# Extra.net
KiCad netlist of a schematic drawn in Altium Designer
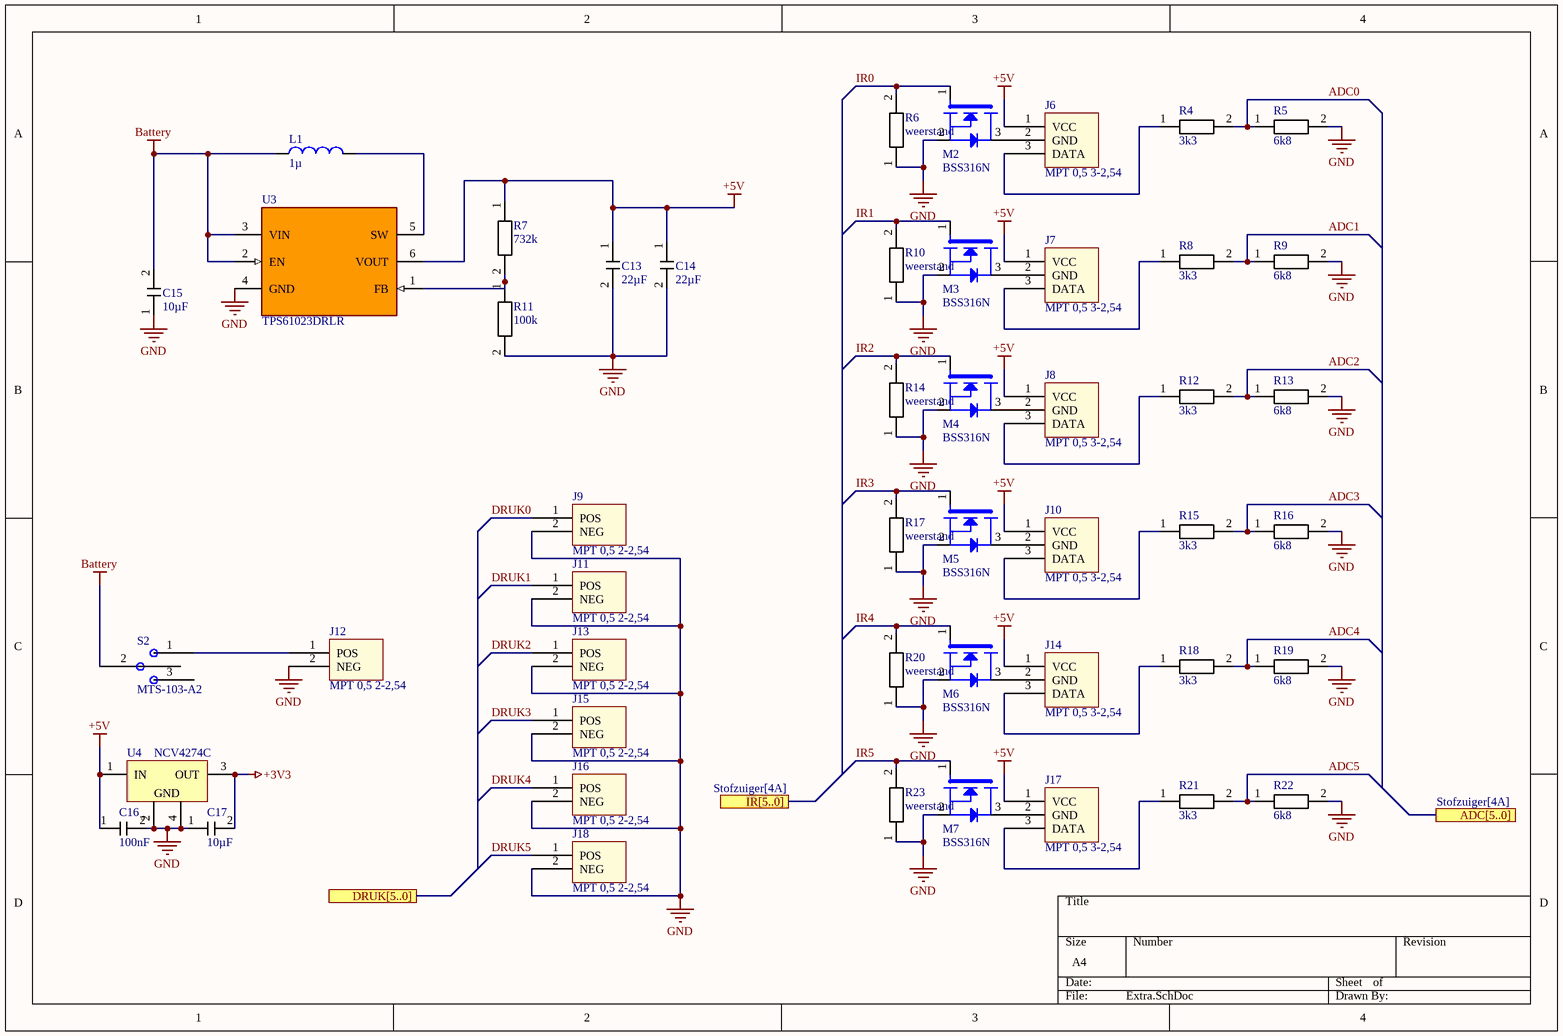
[diagram p0: Extra.SchDoc]

(export (version "E")
  (design (tool "Eeschema 10.0.6"))
  (components
    (comp (ref "C13") (value "22µF") (footprint "0603") (libsource (lib "Schlib1") (part "cap")))
    (comp (ref "C14") (value "22µF") (footprint "0603") (libsource (lib "Schlib1") (part "cap")))
    (comp (ref "C15") (value "10µF") (footprint "0603") (libsource (lib "Schlib1") (part "cap")))
    (comp (ref "C16") (value "100nF") (footprint "0603") (libsource (lib "Schlib1") (part "cap")))
    (comp (ref "C17") (value "10µF") (footprint "0603") (libsource (lib "Schlib1") (part "cap")))
    (comp (ref "J6")
      (value "MPT 0,5 3-2,54")
      (footprint "MPT 0,5 3-2,54")
      (libsource (lib "Schlib1") (part "MPT 0,5 3-2,54"))
    )
    (comp (ref "J7")
      (value "MPT 0,5 3-2,54")
      (footprint "MPT 0,5 3-2,54")
      (libsource (lib "Schlib1") (part "MPT 0,5 3-2,54"))
    )
    (comp (ref "J8")
      (value "MPT 0,5 3-2,54")
      (footprint "MPT 0,5 3-2,54")
      (libsource (lib "Schlib1") (part "MPT 0,5 3-2,54"))
    )
    (comp (ref "J9")
      (value "MPT 0,5 2-2,54")
      (footprint "MPT 0,5 2-2,54")
      (libsource (lib "Schlib1") (part "MPT 0,5 2-2,54"))
    )
    (comp (ref "J10")
      (value "MPT 0,5 3-2,54")
      (footprint "MPT 0,5 3-2,54")
      (libsource (lib "Schlib1") (part "MPT 0,5 3-2,54"))
    )
    (comp (ref "J11")
      (value "MPT 0,5 2-2,54")
      (footprint "MPT 0,5 2-2,54")
      (libsource (lib "Schlib1") (part "MPT 0,5 2-2,54"))
    )
    (comp (ref "J12")
      (value "MPT 0,5 2-2,54")
      (footprint "MPT 0,5 2-2,54")
      (libsource (lib "Schlib1") (part "MPT 0,5 2-2,54"))
    )
    (comp (ref "J13")
      (value "MPT 0,5 2-2,54")
      (footprint "MPT 0,5 2-2,54")
      (libsource (lib "Schlib1") (part "MPT 0,5 2-2,54"))
    )
    (comp (ref "J14")
      (value "MPT 0,5 3-2,54")
      (footprint "MPT 0,5 3-2,54")
      (libsource (lib "Schlib1") (part "MPT 0,5 3-2,54"))
    )
    (comp (ref "J15")
      (value "MPT 0,5 2-2,54")
      (footprint "MPT 0,5 2-2,54")
      (libsource (lib "Schlib1") (part "MPT 0,5 2-2,54"))
    )
    (comp (ref "J16")
      (value "MPT 0,5 2-2,54")
      (footprint "MPT 0,5 2-2,54")
      (libsource (lib "Schlib1") (part "MPT 0,5 2-2,54"))
    )
    (comp (ref "J17")
      (value "MPT 0,5 3-2,54")
      (footprint "MPT 0,5 3-2,54")
      (libsource (lib "Schlib1") (part "MPT 0,5 3-2,54"))
    )
    (comp (ref "J18")
      (value "MPT 0,5 2-2,54")
      (footprint "MPT 0,5 2-2,54")
      (libsource (lib "Schlib1") (part "MPT 0,5 2-2,54"))
    )
    (comp (ref "L1") (value "1µ") (footprint "0603") (libsource (lib "Schlib1") (part "spoel")))
    (comp (ref "M2") (value "BSS316N") (footprint "BSS316N") (libsource (lib "Schlib1") (part "BSS316N")))
    (comp (ref "M3") (value "BSS316N") (footprint "BSS316N") (libsource (lib "Schlib1") (part "BSS316N")))
    (comp (ref "M4") (value "BSS316N") (footprint "BSS316N") (libsource (lib "Schlib1") (part "BSS316N")))
    (comp (ref "M5") (value "BSS316N") (footprint "BSS316N") (libsource (lib "Schlib1") (part "BSS316N")))
    (comp (ref "M6") (value "BSS316N") (footprint "BSS316N") (libsource (lib "Schlib1") (part "BSS316N")))
    (comp (ref "M7") (value "BSS316N") (footprint "BSS316N") (libsource (lib "Schlib1") (part "BSS316N")))
    (comp (ref "R4") (value "3k3") (footprint "0603") (libsource (lib "Schlib1") (part "weerstand")))
    (comp (ref "R5") (value "6k8") (footprint "0603") (libsource (lib "Schlib1") (part "weerstand")))
    (comp (ref "R6") (value "weerstand") (footprint "0603") (libsource (lib "Schlib1") (part "weerstand")))
    (comp (ref "R7") (value "732k") (footprint "0603") (libsource (lib "Schlib1") (part "weerstand")))
    (comp (ref "R8") (value "3k3") (footprint "0603") (libsource (lib "Schlib1") (part "weerstand")))
    (comp (ref "R9") (value "6k8") (footprint "0603") (libsource (lib "Schlib1") (part "weerstand")))
    (comp (ref "R10") (value "weerstand") (footprint "0603") (libsource (lib "Schlib1") (part "weerstand")))
    (comp (ref "R11") (value "100k") (footprint "0603") (libsource (lib "Schlib1") (part "weerstand")))
    (comp (ref "R12") (value "3k3") (footprint "0603") (libsource (lib "Schlib1") (part "weerstand")))
    (comp (ref "R13") (value "6k8") (footprint "0603") (libsource (lib "Schlib1") (part "weerstand")))
    (comp (ref "R14") (value "weerstand") (footprint "0603") (libsource (lib "Schlib1") (part "weerstand")))
    (comp (ref "R15") (value "3k3") (footprint "0603") (libsource (lib "Schlib1") (part "weerstand")))
    (comp (ref "R16") (value "6k8") (footprint "0603") (libsource (lib "Schlib1") (part "weerstand")))
    (comp (ref "R17") (value "weerstand") (footprint "0603") (libsource (lib "Schlib1") (part "weerstand")))
    (comp (ref "R18") (value "3k3") (footprint "0603") (libsource (lib "Schlib1") (part "weerstand")))
    (comp (ref "R19") (value "6k8") (footprint "0603") (libsource (lib "Schlib1") (part "weerstand")))
    (comp (ref "R20") (value "weerstand") (footprint "0603") (libsource (lib "Schlib1") (part "weerstand")))
    (comp (ref "R21") (value "3k3") (footprint "0603") (libsource (lib "Schlib1") (part "weerstand")))
    (comp (ref "R22") (value "6k8") (footprint "0603") (libsource (lib "Schlib1") (part "weerstand")))
    (comp (ref "R23") (value "weerstand") (footprint "0603") (libsource (lib "Schlib1") (part "weerstand")))
    (comp (ref "S2")
      (value "MTS-103-A2")
      (footprint "MTS-103-A2")
      (libsource (lib "Schlib1") (part "MTS-103-A2"))
    )
    (comp (ref "U3")
      (value "TPS61023DRLR")
      (footprint "TPS61023DRLR")
      (libsource (lib "Schlib1") (part "TPS61023DRLR"))
    )
    (comp (ref "U4") (value "NCV4274C") (footprint "NCV4274C") (libsource (lib "Schlib1") (part "NCV4274C")))
  )
  (nets
    (net (code "1") (name "+3V3") (class "Default")
      (node (ref "C17") (pin "2") (pinfunction "G_2") (pintype "passive"))
      (node (ref "U4") (pin "3") (pinfunction "OUT_3") (pintype "power_in"))
    )
    (net (code "2") (name "+5V") (class "Default")
      (node (ref "C13") (pin "1") (pinfunction "G_1") (pintype "passive"))
      (node (ref "C14") (pin "1") (pinfunction "G_1") (pintype "passive"))
      (node (ref "C16") (pin "1") (pinfunction "G_1") (pintype "passive"))
      (node (ref "J10") (pin "1") (pinfunction "VCC_1") (pintype "passive"))
      (node (ref "J14") (pin "1") (pinfunction "VCC_1") (pintype "passive"))
      (node (ref "J17") (pin "1") (pinfunction "VCC_1") (pintype "passive"))
      (node (ref "J6") (pin "1") (pinfunction "VCC_1") (pintype "passive"))
      (node (ref "J7") (pin "1") (pinfunction "VCC_1") (pintype "passive"))
      (node (ref "J8") (pin "1") (pinfunction "VCC_1") (pintype "passive"))
      (node (ref "R7") (pin "1") (pinfunction "1_1") (pintype "passive"))
      (node (ref "U3") (pin "6") (pinfunction "VOUT_6") (pintype "power_in"))
      (node (ref "U4") (pin "1") (pinfunction "IN_1") (pintype "power_in"))
    )
    (net (code "3") (name "/ADC0") (class "Default")
      (node (ref "R4") (pin "2") (pinfunction "G_2") (pintype "passive"))
      (node (ref "R5") (pin "1") (pinfunction "1_1") (pintype "passive"))
    )
    (net (code "4") (name "/ADC1") (class "Default")
      (node (ref "R8") (pin "2") (pinfunction "G_2") (pintype "passive"))
      (node (ref "R9") (pin "1") (pinfunction "1_1") (pintype "passive"))
    )
    (net (code "5") (name "/ADC2") (class "Default")
      (node (ref "R12") (pin "2") (pinfunction "G_2") (pintype "passive"))
      (node (ref "R13") (pin "1") (pinfunction "1_1") (pintype "passive"))
    )
    (net (code "6") (name "/ADC3") (class "Default")
      (node (ref "R15") (pin "2") (pinfunction "G_2") (pintype "passive"))
      (node (ref "R16") (pin "1") (pinfunction "1_1") (pintype "passive"))
    )
    (net (code "7") (name "/ADC4") (class "Default")
      (node (ref "R18") (pin "2") (pinfunction "G_2") (pintype "passive"))
      (node (ref "R19") (pin "1") (pinfunction "1_1") (pintype "passive"))
    )
    (net (code "8") (name "/ADC5") (class "Default")
      (node (ref "R21") (pin "2") (pinfunction "G_2") (pintype "passive"))
      (node (ref "R22") (pin "1") (pinfunction "1_1") (pintype "passive"))
    )
    (net (code "10") (name "/DRUK0") (class "Default")
      (node (ref "J9") (pin "1") (pinfunction "POS_1") (pintype "passive"))
    )
    (net (code "11") (name "/DRUK1") (class "Default")
      (node (ref "J11") (pin "1") (pinfunction "POS_1") (pintype "passive"))
    )
    (net (code "12") (name "/DRUK2") (class "Default")
      (node (ref "J13") (pin "1") (pinfunction "POS_1") (pintype "passive"))
    )
    (net (code "13") (name "/DRUK3") (class "Default")
      (node (ref "J15") (pin "1") (pinfunction "POS_1") (pintype "passive"))
    )
    (net (code "14") (name "/DRUK4") (class "Default")
      (node (ref "J16") (pin "1") (pinfunction "POS_1") (pintype "passive"))
    )
    (net (code "15") (name "/DRUK5") (class "Default")
      (node (ref "J18") (pin "1") (pinfunction "POS_1") (pintype "passive"))
    )
    (net (code "17") (name "/IR0") (class "Default")
      (node (ref "M2") (pin "1") (pinfunction "G_1") (pintype "passive"))
      (node (ref "R6") (pin "2") (pinfunction "G_2") (pintype "passive"))
    )
    (net (code "18") (name "/IR1") (class "Default")
      (node (ref "M3") (pin "1") (pinfunction "G_1") (pintype "passive"))
      (node (ref "R10") (pin "2") (pinfunction "G_2") (pintype "passive"))
    )
    (net (code "19") (name "/IR2") (class "Default")
      (node (ref "M4") (pin "1") (pinfunction "G_1") (pintype "passive"))
      (node (ref "R14") (pin "2") (pinfunction "G_2") (pintype "passive"))
    )
    (net (code "20") (name "/IR3") (class "Default")
      (node (ref "M5") (pin "1") (pinfunction "G_1") (pintype "passive"))
      (node (ref "R17") (pin "2") (pinfunction "G_2") (pintype "passive"))
    )
    (net (code "21") (name "/IR4") (class "Default")
      (node (ref "M6") (pin "1") (pinfunction "G_1") (pintype "passive"))
      (node (ref "R20") (pin "2") (pinfunction "G_2") (pintype "passive"))
    )
    (net (code "22") (name "/IR5") (class "Default")
      (node (ref "M7") (pin "1") (pinfunction "G_1") (pintype "passive"))
      (node (ref "R23") (pin "2") (pinfunction "G_2") (pintype "passive"))
    )
    (net (code "24") (name "Battery") (class "Default")
      (node (ref "C15") (pin "2") (pinfunction "G_2") (pintype "passive"))
      (node (ref "L1") (pin "1") (pinfunction "1_1") (pintype "passive"))
      (node (ref "S2") (pin "2") (pinfunction "2_2") (pintype "passive"))
      (node (ref "U3") (pin "2") (pinfunction "EN_2") (pintype "input"))
      (node (ref "U3") (pin "3") (pinfunction "VIN_3") (pintype "power_in"))
    )
    (net (code "25") (name "GND") (class "Default")
      (node (ref "C13") (pin "2") (pinfunction "G_2") (pintype "passive"))
      (node (ref "C14") (pin "2") (pinfunction "G_2") (pintype "passive"))
      (node (ref "C15") (pin "1") (pinfunction "G_1") (pintype "passive"))
      (node (ref "C16") (pin "2") (pinfunction "G_2") (pintype "passive"))
      (node (ref "C17") (pin "1") (pinfunction "G_1") (pintype "passive"))
      (node (ref "J11") (pin "2") (pinfunction "NEG_2") (pintype "passive"))
      (node (ref "J12") (pin "2") (pinfunction "NEG_2") (pintype "passive"))
      (node (ref "J13") (pin "2") (pinfunction "NEG_2") (pintype "passive"))
      (node (ref "J15") (pin "2") (pinfunction "NEG_2") (pintype "passive"))
      (node (ref "J16") (pin "2") (pinfunction "NEG_2") (pintype "passive"))
      (node (ref "J18") (pin "2") (pinfunction "NEG_2") (pintype "passive"))
      (node (ref "J9") (pin "2") (pinfunction "NEG_2") (pintype "passive"))
      (node (ref "M2") (pin "2") (pinfunction "S_2") (pintype "passive"))
      (node (ref "M3") (pin "2") (pinfunction "S_2") (pintype "passive"))
      (node (ref "M4") (pin "2") (pinfunction "S_2") (pintype "passive"))
      (node (ref "M5") (pin "2") (pinfunction "S_2") (pintype "passive"))
      (node (ref "M6") (pin "2") (pinfunction "S_2") (pintype "passive"))
      (node (ref "M7") (pin "2") (pinfunction "S_2") (pintype "passive"))
      (node (ref "R10") (pin "1") (pinfunction "1_1") (pintype "passive"))
      (node (ref "R11") (pin "2") (pinfunction "G_2") (pintype "passive"))
      (node (ref "R13") (pin "2") (pinfunction "G_2") (pintype "passive"))
      (node (ref "R14") (pin "1") (pinfunction "1_1") (pintype "passive"))
      (node (ref "R16") (pin "2") (pinfunction "G_2") (pintype "passive"))
      (node (ref "R17") (pin "1") (pinfunction "1_1") (pintype "passive"))
      (node (ref "R19") (pin "2") (pinfunction "G_2") (pintype "passive"))
      (node (ref "R20") (pin "1") (pinfunction "1_1") (pintype "passive"))
      (node (ref "R22") (pin "2") (pinfunction "G_2") (pintype "passive"))
      (node (ref "R23") (pin "1") (pinfunction "1_1") (pintype "passive"))
      (node (ref "R5") (pin "2") (pinfunction "G_2") (pintype "passive"))
      (node (ref "R6") (pin "1") (pinfunction "1_1") (pintype "passive"))
      (node (ref "R9") (pin "2") (pinfunction "G_2") (pintype "passive"))
      (node (ref "U3") (pin "4") (pinfunction "GND_4") (pintype "power_in"))
      (node (ref "U4") (pin "2") (pinfunction "GND_2") (pintype "power_in"))
      (node (ref "U4") (pin "4") (pinfunction "GND_4") (pintype "power_in"))
    )
    (net (code "26") (name "Net-(J6-DATA)") (class "Default")
      (node (ref "J6") (pin "3") (pinfunction "DATA_3") (pintype "passive"))
      (node (ref "R4") (pin "1") (pinfunction "1_1") (pintype "passive"))
    )
    (net (code "27") (name "Net-(J6-GND)") (class "Default")
      (node (ref "J6") (pin "2") (pinfunction "GND_2") (pintype "passive"))
      (node (ref "M2") (pin "3") (pinfunction "D_3") (pintype "passive"))
    )
    (net (code "28") (name "Net-(J7-DATA)") (class "Default")
      (node (ref "J7") (pin "3") (pinfunction "DATA_3") (pintype "passive"))
      (node (ref "R8") (pin "1") (pinfunction "1_1") (pintype "passive"))
    )
    (net (code "29") (name "Net-(J7-GND)") (class "Default")
      (node (ref "J7") (pin "2") (pinfunction "GND_2") (pintype "passive"))
      (node (ref "M3") (pin "3") (pinfunction "D_3") (pintype "passive"))
    )
    (net (code "30") (name "Net-(J8-DATA)") (class "Default")
      (node (ref "J8") (pin "3") (pinfunction "DATA_3") (pintype "passive"))
      (node (ref "R12") (pin "1") (pinfunction "1_1") (pintype "passive"))
    )
    (net (code "31") (name "Net-(J8-GND)") (class "Default")
      (node (ref "J8") (pin "2") (pinfunction "GND_2") (pintype "passive"))
      (node (ref "M4") (pin "3") (pinfunction "D_3") (pintype "passive"))
    )
    (net (code "32") (name "Net-(J10-DATA)") (class "Default")
      (node (ref "J10") (pin "3") (pinfunction "DATA_3") (pintype "passive"))
      (node (ref "R15") (pin "1") (pinfunction "1_1") (pintype "passive"))
    )
    (net (code "33") (name "Net-(J10-GND)") (class "Default")
      (node (ref "J10") (pin "2") (pinfunction "GND_2") (pintype "passive"))
      (node (ref "M5") (pin "3") (pinfunction "D_3") (pintype "passive"))
    )
    (net (code "34") (name "Net-(J12-POS)") (class "Default")
      (node (ref "J12") (pin "1") (pinfunction "POS_1") (pintype "passive"))
      (node (ref "S2") (pin "1") (pinfunction "1_1") (pintype "passive"))
    )
    (net (code "35") (name "Net-(J14-DATA)") (class "Default")
      (node (ref "J14") (pin "3") (pinfunction "DATA_3") (pintype "passive"))
      (node (ref "R18") (pin "1") (pinfunction "1_1") (pintype "passive"))
    )
    (net (code "36") (name "Net-(J14-GND)") (class "Default")
      (node (ref "J14") (pin "2") (pinfunction "GND_2") (pintype "passive"))
      (node (ref "M6") (pin "3") (pinfunction "D_3") (pintype "passive"))
    )
    (net (code "37") (name "Net-(J17-DATA)") (class "Default")
      (node (ref "J17") (pin "3") (pinfunction "DATA_3") (pintype "passive"))
      (node (ref "R21") (pin "1") (pinfunction "1_1") (pintype "passive"))
    )
    (net (code "38") (name "Net-(J17-GND)") (class "Default")
      (node (ref "J17") (pin "2") (pinfunction "GND_2") (pintype "passive"))
      (node (ref "M7") (pin "3") (pinfunction "D_3") (pintype "passive"))
    )
    (net (code "39") (name "Net-(R7-G)") (class "Default")
      (node (ref "R11") (pin "1") (pinfunction "1_1") (pintype "passive"))
      (node (ref "R7") (pin "2") (pinfunction "G_2") (pintype "passive"))
      (node (ref "U3") (pin "1") (pinfunction "FB_1") (pintype "input"))
    )
    (net (code "40") (name "Net-(U3-SW)") (class "Default")
      (node (ref "L1") (pin "2") (pinfunction "2_2") (pintype "passive"))
      (node (ref "U3") (pin "5") (pinfunction "SW_5") (pintype "power_in"))
    )
    (net (code "41") (name "unconnected-(S2-Pad3)") (class "Default")
      (node (ref "S2") (pin "3") (pinfunction "3_3") (pintype "passive"))
    )
  )
)
